# 6packRev1D.net
KiCad netlist of a schematic drawn in EAGLE
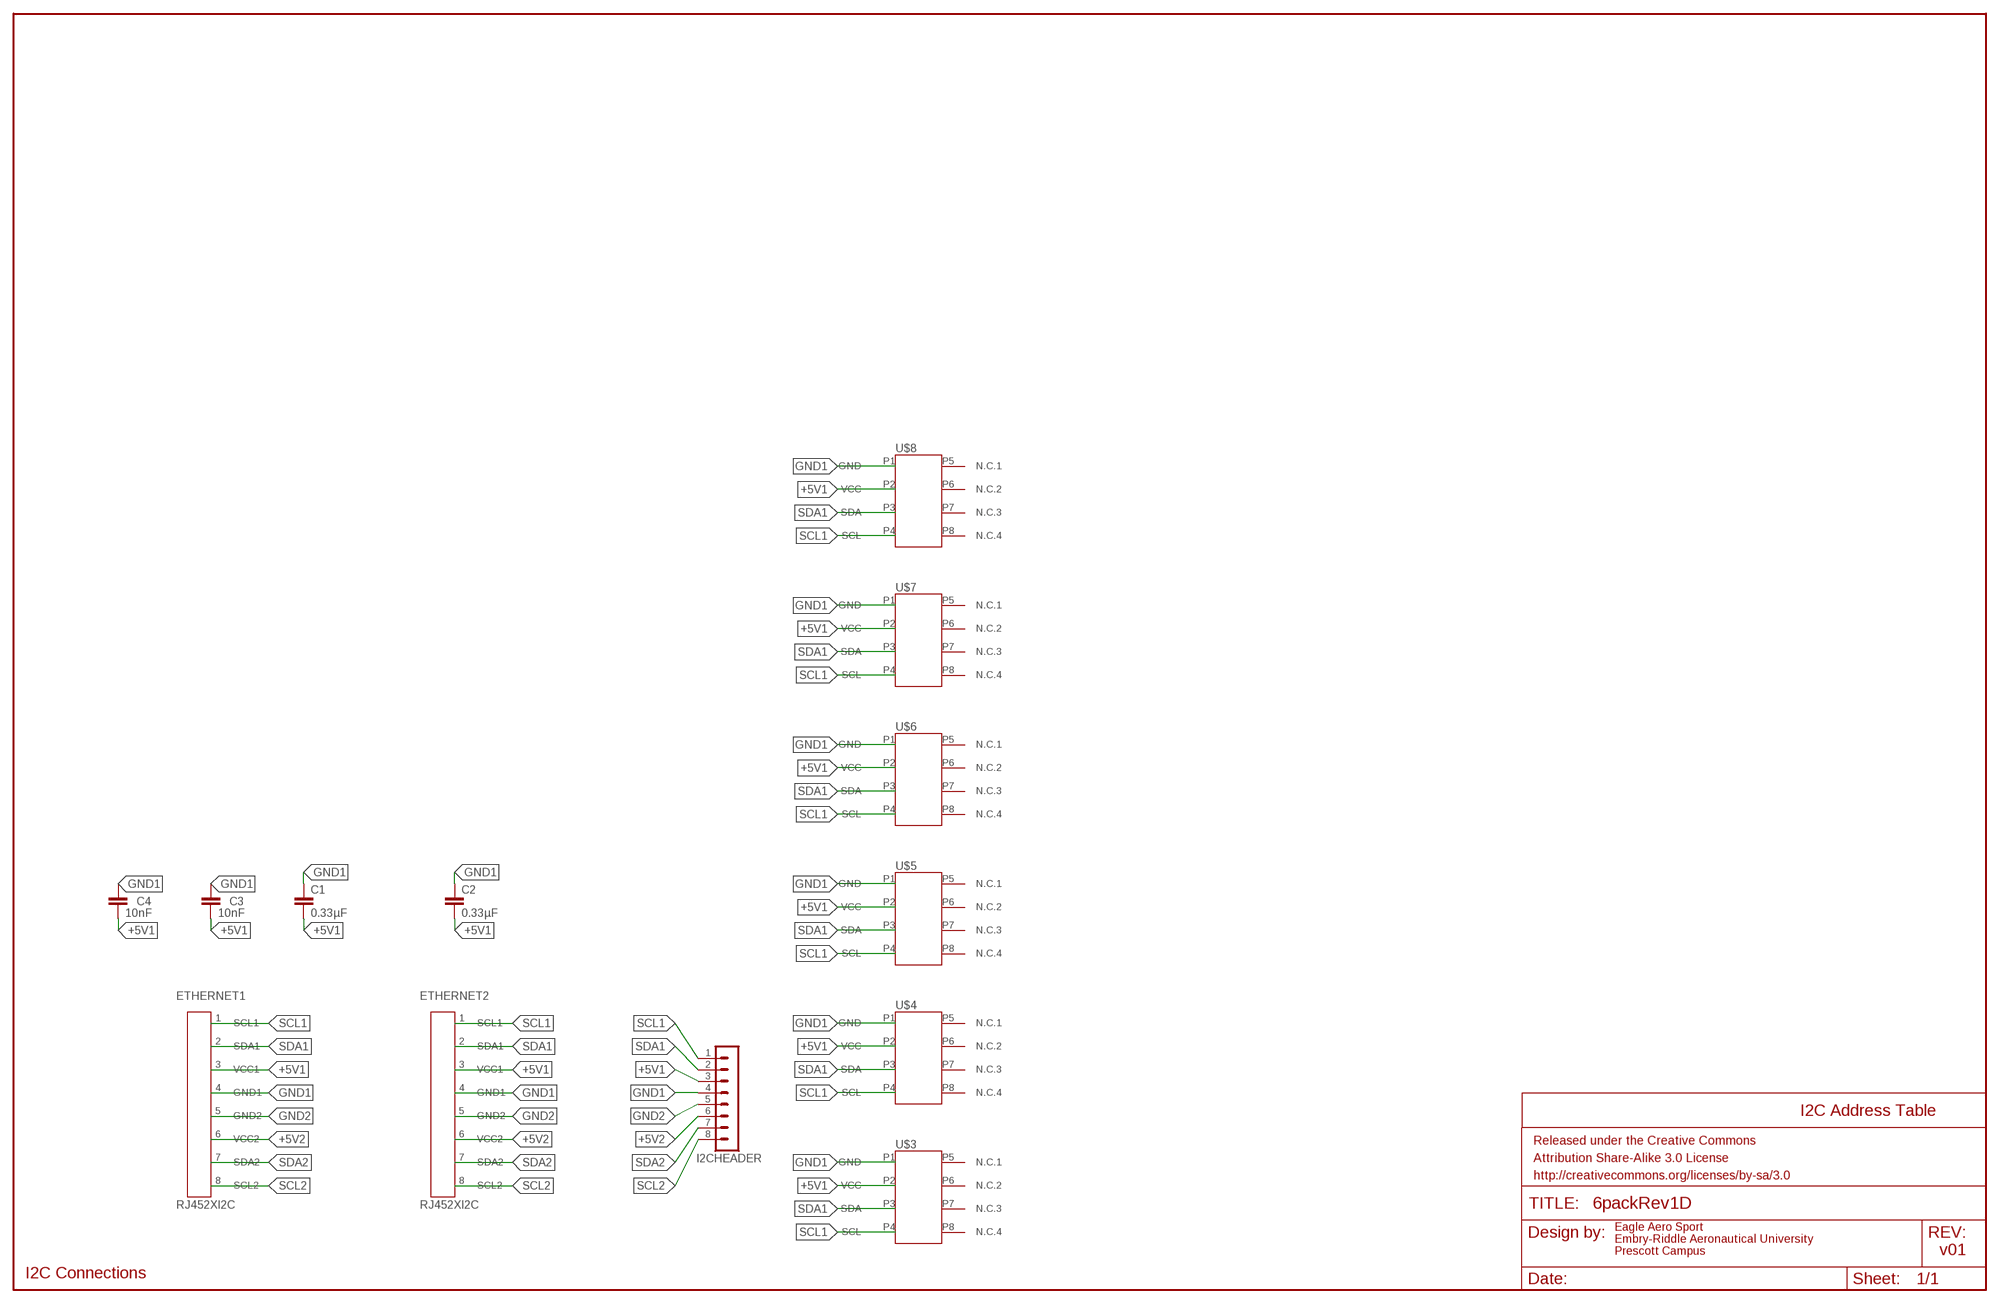
[diagram p0: schematic, sheet 1]

(export (version "E")
  (design (tool "Eeschema 10.0.6"))
  (components
    (comp (ref "C1")
      (value "0.33µF")
      (footprint "eagle-import:0805")
      (libsource (lib "eagle-import") (part "0.33UF/330NF-0805-50V-10%"))
    )
    (comp (ref "C2")
      (value "0.33µF")
      (footprint "eagle-import:0805")
      (libsource (lib "eagle-import") (part "0.33UF/330NF-0805-50V-10%"))
    )
    (comp (ref "C3")
      (value "10nF")
      (footprint "eagle-import:CAP-PTH-10MM")
      (libsource (lib "eagle-import") (part "10NF-PTH-10MM-10000V-1-%"))
    )
    (comp (ref "C4")
      (value "10nF")
      (footprint "eagle-import:CAP-PTH-10MM")
      (libsource (lib "eagle-import") (part "10NF-PTH-10MM-10000V-1-%"))
    )
    (comp (ref "ETHERNET1")
      (value "RJ452XI2C")
      (footprint "eagle-import:RJ45-8")
      (libsource (lib "eagle-import") (part "RJ452XI2C"))
    )
    (comp (ref "ETHERNET2")
      (value "RJ452XI2C")
      (footprint "eagle-import:RJ45-8")
      (libsource (lib "eagle-import") (part "RJ452XI2C"))
    )
    (comp (ref "FRAME1")
      (value "FRAME-LEDGER")
      (footprint "eagle-import:CREATIVE_COMMONS")
      (libsource (lib "eagle-import") (part "FRAME-LEDGER"))
    )
    (comp (ref "I2CHEADER")
      (value "MA08-1")
      (footprint "eagle-import:MA08-1")
      (libsource (lib "eagle-import") (part "MA08-1"))
    )
    (comp (ref "U$3")
      (value "AMS5915")
      (footprint "eagle-import:DIP8W")
      (libsource (lib "eagle-import") (part "AMS5915"))
    )
    (comp (ref "U$4")
      (value "AMS5915")
      (footprint "eagle-import:DIP8W")
      (libsource (lib "eagle-import") (part "AMS5915"))
    )
    (comp (ref "U$5")
      (value "AMS5915")
      (footprint "eagle-import:DIP8W")
      (libsource (lib "eagle-import") (part "AMS5915"))
    )
    (comp (ref "U$6")
      (value "AMS5915")
      (footprint "eagle-import:DIP8W")
      (libsource (lib "eagle-import") (part "AMS5915"))
    )
    (comp (ref "U$7")
      (value "AMS5915")
      (footprint "eagle-import:DIP8W")
      (libsource (lib "eagle-import") (part "AMS5915"))
    )
    (comp (ref "U$8")
      (value "AMS5915")
      (footprint "eagle-import:DIP8W")
      (libsource (lib "eagle-import") (part "AMS5915"))
    )
  )
  (nets
    (net (code "1") (name "+5V1") (class "Default")
      (node (ref "C1") (pin "2") (pinfunction "2_2") (pintype "passive"))
      (node (ref "C2") (pin "2") (pinfunction "2_2") (pintype "passive"))
      (node (ref "C3") (pin "2") (pinfunction "2_2") (pintype "passive"))
      (node (ref "C4") (pin "2") (pinfunction "2_2") (pintype "passive"))
      (node (ref "ETHERNET1") (pin "3") (pinfunction "VCC1_3") (pintype "bidirectional"))
      (node (ref "ETHERNET2") (pin "3") (pinfunction "VCC1_3") (pintype "bidirectional"))
      (node (ref "I2CHEADER") (pin "3") (pinfunction "3_3") (pintype "passive"))
      (node (ref "U$3") (pin "P2") (pinfunction "VCC_P2") (pintype "power_in"))
      (node (ref "U$4") (pin "P2") (pinfunction "VCC_P2") (pintype "power_in"))
      (node (ref "U$5") (pin "P2") (pinfunction "VCC_P2") (pintype "power_in"))
      (node (ref "U$6") (pin "P2") (pinfunction "VCC_P2") (pintype "power_in"))
      (node (ref "U$7") (pin "P2") (pinfunction "VCC_P2") (pintype "power_in"))
      (node (ref "U$8") (pin "P2") (pinfunction "VCC_P2") (pintype "power_in"))
    )
    (net (code "2") (name "+5V2") (class "Default")
      (node (ref "ETHERNET1") (pin "6") (pinfunction "VCC2_6") (pintype "bidirectional"))
      (node (ref "ETHERNET2") (pin "6") (pinfunction "VCC2_6") (pintype "bidirectional"))
      (node (ref "I2CHEADER") (pin "6") (pinfunction "6_6") (pintype "passive"))
    )
    (net (code "3") (name "GND1") (class "Default")
      (node (ref "C1") (pin "1") (pinfunction "1_1") (pintype "passive"))
      (node (ref "C2") (pin "1") (pinfunction "1_1") (pintype "passive"))
      (node (ref "C3") (pin "1") (pinfunction "1_1") (pintype "passive"))
      (node (ref "C4") (pin "1") (pinfunction "1_1") (pintype "passive"))
      (node (ref "ETHERNET1") (pin "4") (pinfunction "GND1_4") (pintype "bidirectional"))
      (node (ref "ETHERNET2") (pin "4") (pinfunction "GND1_4") (pintype "bidirectional"))
      (node (ref "I2CHEADER") (pin "4") (pinfunction "4_4") (pintype "passive"))
      (node (ref "U$3") (pin "P1") (pinfunction "GND_P1") (pintype "bidirectional"))
      (node (ref "U$4") (pin "P1") (pinfunction "GND_P1") (pintype "bidirectional"))
      (node (ref "U$5") (pin "P1") (pinfunction "GND_P1") (pintype "bidirectional"))
      (node (ref "U$6") (pin "P1") (pinfunction "GND_P1") (pintype "bidirectional"))
      (node (ref "U$7") (pin "P1") (pinfunction "GND_P1") (pintype "bidirectional"))
      (node (ref "U$8") (pin "P1") (pinfunction "GND_P1") (pintype "bidirectional"))
    )
    (net (code "4") (name "GND2") (class "Default")
      (node (ref "ETHERNET1") (pin "5") (pinfunction "GND2_5") (pintype "bidirectional"))
      (node (ref "ETHERNET2") (pin "5") (pinfunction "GND2_5") (pintype "bidirectional"))
      (node (ref "I2CHEADER") (pin "5") (pinfunction "5_5") (pintype "passive"))
    )
    (net (code "5") (name "SCL1") (class "Default")
      (node (ref "ETHERNET1") (pin "1") (pinfunction "SCL1_1") (pintype "bidirectional"))
      (node (ref "ETHERNET2") (pin "1") (pinfunction "SCL1_1") (pintype "bidirectional"))
      (node (ref "I2CHEADER") (pin "1") (pinfunction "1_1") (pintype "passive"))
      (node (ref "U$3") (pin "P4") (pinfunction "SCL_P4") (pintype "bidirectional"))
      (node (ref "U$4") (pin "P4") (pinfunction "SCL_P4") (pintype "bidirectional"))
      (node (ref "U$5") (pin "P4") (pinfunction "SCL_P4") (pintype "bidirectional"))
      (node (ref "U$6") (pin "P4") (pinfunction "SCL_P4") (pintype "bidirectional"))
      (node (ref "U$7") (pin "P4") (pinfunction "SCL_P4") (pintype "bidirectional"))
      (node (ref "U$8") (pin "P4") (pinfunction "SCL_P4") (pintype "bidirectional"))
    )
    (net (code "6") (name "SCL2") (class "Default")
      (node (ref "ETHERNET1") (pin "8") (pinfunction "SCL2_8") (pintype "bidirectional"))
      (node (ref "ETHERNET2") (pin "8") (pinfunction "SCL2_8") (pintype "bidirectional"))
      (node (ref "I2CHEADER") (pin "8") (pinfunction "8_8") (pintype "passive"))
    )
    (net (code "7") (name "SDA1") (class "Default")
      (node (ref "ETHERNET1") (pin "2") (pinfunction "SDA1_2") (pintype "bidirectional"))
      (node (ref "ETHERNET2") (pin "2") (pinfunction "SDA1_2") (pintype "bidirectional"))
      (node (ref "I2CHEADER") (pin "2") (pinfunction "2_2") (pintype "passive"))
      (node (ref "U$3") (pin "P3") (pinfunction "SDA_P3") (pintype "bidirectional"))
      (node (ref "U$4") (pin "P3") (pinfunction "SDA_P3") (pintype "bidirectional"))
      (node (ref "U$5") (pin "P3") (pinfunction "SDA_P3") (pintype "bidirectional"))
      (node (ref "U$6") (pin "P3") (pinfunction "SDA_P3") (pintype "bidirectional"))
      (node (ref "U$7") (pin "P3") (pinfunction "SDA_P3") (pintype "bidirectional"))
      (node (ref "U$8") (pin "P3") (pinfunction "SDA_P3") (pintype "bidirectional"))
    )
    (net (code "8") (name "SDA2") (class "Default")
      (node (ref "ETHERNET1") (pin "7") (pinfunction "SDA2_7") (pintype "bidirectional"))
      (node (ref "ETHERNET2") (pin "7") (pinfunction "SDA2_7") (pintype "bidirectional"))
      (node (ref "I2CHEADER") (pin "7") (pinfunction "7_7") (pintype "passive"))
    )
    (net (code "9") (name "unconnected-(U$3-N.C.1-PadP5)") (class "Default")
      (node (ref "U$3") (pin "P5") (pinfunction "N.C.1_P5") (pintype "no_connect"))
    )
    (net (code "10") (name "unconnected-(U$3-N.C.2-PadP6)") (class "Default")
      (node (ref "U$3") (pin "P6") (pinfunction "N.C.2_P6") (pintype "no_connect"))
    )
    (net (code "11") (name "unconnected-(U$3-N.C.3-PadP7)") (class "Default")
      (node (ref "U$3") (pin "P7") (pinfunction "N.C.3_P7") (pintype "no_connect"))
    )
    (net (code "12") (name "unconnected-(U$3-N.C.4-PadP8)") (class "Default")
      (node (ref "U$3") (pin "P8") (pinfunction "N.C.4_P8") (pintype "no_connect"))
    )
    (net (code "13") (name "unconnected-(U$4-N.C.1-PadP5)") (class "Default")
      (node (ref "U$4") (pin "P5") (pinfunction "N.C.1_P5") (pintype "no_connect"))
    )
    (net (code "14") (name "unconnected-(U$4-N.C.2-PadP6)") (class "Default")
      (node (ref "U$4") (pin "P6") (pinfunction "N.C.2_P6") (pintype "no_connect"))
    )
    (net (code "15") (name "unconnected-(U$4-N.C.3-PadP7)") (class "Default")
      (node (ref "U$4") (pin "P7") (pinfunction "N.C.3_P7") (pintype "no_connect"))
    )
    (net (code "16") (name "unconnected-(U$4-N.C.4-PadP8)") (class "Default")
      (node (ref "U$4") (pin "P8") (pinfunction "N.C.4_P8") (pintype "no_connect"))
    )
    (net (code "17") (name "unconnected-(U$5-N.C.1-PadP5)") (class "Default")
      (node (ref "U$5") (pin "P5") (pinfunction "N.C.1_P5") (pintype "no_connect"))
    )
    (net (code "18") (name "unconnected-(U$5-N.C.2-PadP6)") (class "Default")
      (node (ref "U$5") (pin "P6") (pinfunction "N.C.2_P6") (pintype "no_connect"))
    )
    (net (code "19") (name "unconnected-(U$5-N.C.3-PadP7)") (class "Default")
      (node (ref "U$5") (pin "P7") (pinfunction "N.C.3_P7") (pintype "no_connect"))
    )
    (net (code "20") (name "unconnected-(U$5-N.C.4-PadP8)") (class "Default")
      (node (ref "U$5") (pin "P8") (pinfunction "N.C.4_P8") (pintype "no_connect"))
    )
    (net (code "21") (name "unconnected-(U$6-N.C.1-PadP5)") (class "Default")
      (node (ref "U$6") (pin "P5") (pinfunction "N.C.1_P5") (pintype "no_connect"))
    )
    (net (code "22") (name "unconnected-(U$6-N.C.2-PadP6)") (class "Default")
      (node (ref "U$6") (pin "P6") (pinfunction "N.C.2_P6") (pintype "no_connect"))
    )
    (net (code "23") (name "unconnected-(U$6-N.C.3-PadP7)") (class "Default")
      (node (ref "U$6") (pin "P7") (pinfunction "N.C.3_P7") (pintype "no_connect"))
    )
    (net (code "24") (name "unconnected-(U$6-N.C.4-PadP8)") (class "Default")
      (node (ref "U$6") (pin "P8") (pinfunction "N.C.4_P8") (pintype "no_connect"))
    )
    (net (code "25") (name "unconnected-(U$7-N.C.1-PadP5)") (class "Default")
      (node (ref "U$7") (pin "P5") (pinfunction "N.C.1_P5") (pintype "no_connect"))
    )
    (net (code "26") (name "unconnected-(U$7-N.C.2-PadP6)") (class "Default")
      (node (ref "U$7") (pin "P6") (pinfunction "N.C.2_P6") (pintype "no_connect"))
    )
    (net (code "27") (name "unconnected-(U$7-N.C.3-PadP7)") (class "Default")
      (node (ref "U$7") (pin "P7") (pinfunction "N.C.3_P7") (pintype "no_connect"))
    )
    (net (code "28") (name "unconnected-(U$7-N.C.4-PadP8)") (class "Default")
      (node (ref "U$7") (pin "P8") (pinfunction "N.C.4_P8") (pintype "no_connect"))
    )
    (net (code "29") (name "unconnected-(U$8-N.C.1-PadP5)") (class "Default")
      (node (ref "U$8") (pin "P5") (pinfunction "N.C.1_P5") (pintype "no_connect"))
    )
    (net (code "30") (name "unconnected-(U$8-N.C.2-PadP6)") (class "Default")
      (node (ref "U$8") (pin "P6") (pinfunction "N.C.2_P6") (pintype "no_connect"))
    )
    (net (code "31") (name "unconnected-(U$8-N.C.3-PadP7)") (class "Default")
      (node (ref "U$8") (pin "P7") (pinfunction "N.C.3_P7") (pintype "no_connect"))
    )
    (net (code "32") (name "unconnected-(U$8-N.C.4-PadP8)") (class "Default")
      (node (ref "U$8") (pin "P8") (pinfunction "N.C.4_P8") (pintype "no_connect"))
    )
  )
)
